# SCH_gibran_2026-04-14.net
KiCad netlist of a schematic drawn in EasyEDA
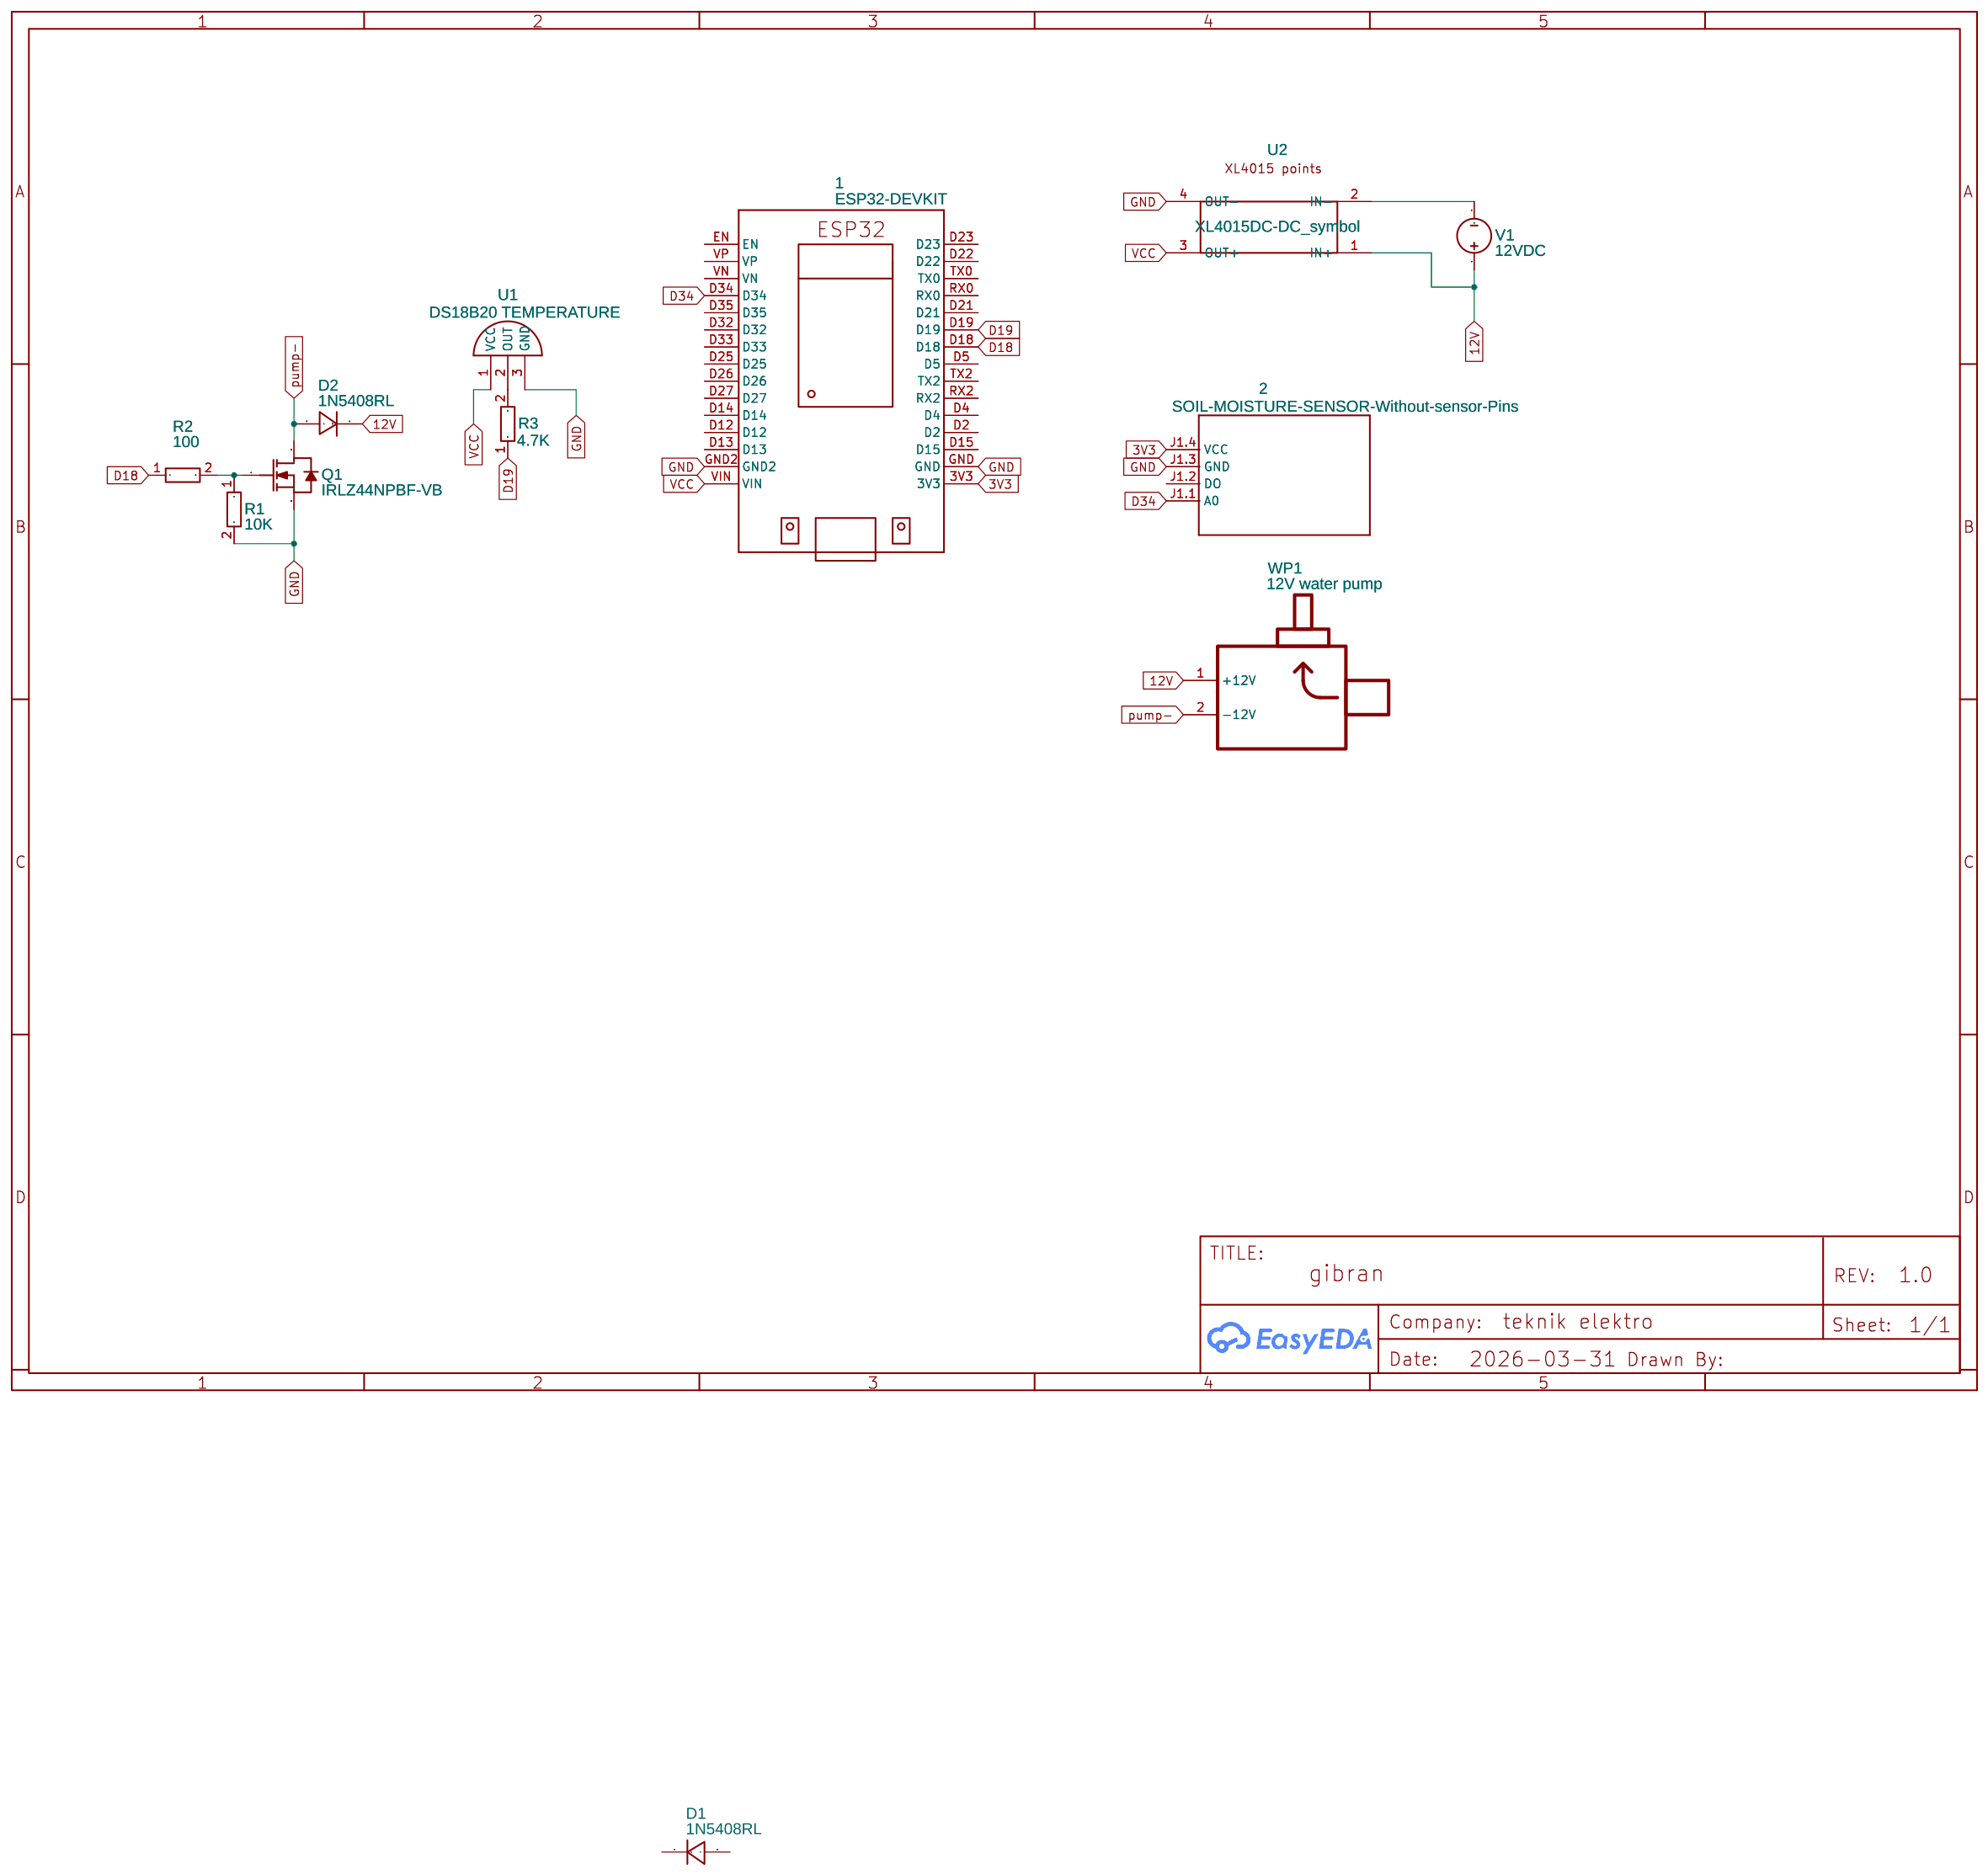
[diagram p0: schematic sheet]

(export (version "E")
  (design (tool "Eeschema 10.0.6"))
  (components
    (comp (ref "1") (value "ESP32-DEVKIT") (libsource (lib "") (part "ESP32-DEVKIT-V1-30PIN")))
    (comp (ref "2")
      (value "SOIL-MOISTURE-SENSOR-Without-sensor-Pins")
      (libsource (lib "") (part "SOIL-MOISTURE-SENSOR-Without-sensor-Pins"))
    )
    (comp (ref "D1") (value "1N5408RL") (libsource (lib "") (part "1N5408RL_1")))
    (comp (ref "D2") (value "1N5408RL") (libsource (lib "") (part "1N5408RL")))
    (comp (ref "Q1")
      (value "IRLZ44NPBF-VB")
      (fields (field (name "Manufacturer") "VBsemi(微碧半导体)"))
      (libsource (lib "") (part "IRLZ44NPBF-VB"))
    )
    (comp (ref "R1")
      (value "10K")
      (fields (field (name "Manufacturer Part") "MF1/4W-330Ω±1% T") (field (name "Manufacturer") "CCO(千志电子)"))
      (libsource (lib "") (part "10K-R-THT"))
    )
    (comp (ref "R2")
      (value "100")
      (fields (field (name "Manufacturer Part") "MF1/4W-330Ω±1% T") (field (name "Manufacturer") "CCO(千志电子)"))
      (libsource (lib "") (part "10K-R-THT_2"))
    )
    (comp (ref "R3")
      (value "4.7K")
      (fields (field (name "Manufacturer Part") "MF1/4W-330Ω±1% T") (field (name "Manufacturer") "CCO(千志电子)"))
      (libsource (lib "") (part "10K-R-THT_1"))
    )
    (comp (ref "U1")
      (value "DS18B20 TEMPERATURE")
      (fields (field (name "Manufacturer Part") "New SchematicLib"))
      (libsource (lib "") (part "DS18B20 TEMPERATURE"))
    )
    (comp (ref "U2") (value "XL4015DC-DC_symbol") (libsource (lib "") (part "XL4015DC-DC_symbol")))
    (comp (ref "V1") (value "12VDC") (libsource (lib "") (part "POWER_SUPPLY_12V COPY COPY")))
    (comp (ref "WP1") (value "12V water pump") (libsource (lib "") (part "12V water pump")))
  )
  (nets
    (net (code "1") (name "3V3") (class "Default")
      (node (ref "1") (pin "3V3") (pinfunction "3V3_3V3") (pintype "unspecified"))
      (node (ref "2") (pin "J1.4") (pinfunction "VCC_J1.4") (pintype "unspecified"))
    )
    (net (code "2") (name "12V") (class "Default")
      (node (ref "D2") (pin "1") (pinfunction "C_1") (pintype "unspecified"))
      (node (ref "U2") (pin "1") (pinfunction "IN+_1") (pintype "unspecified"))
      (node (ref "V1") (pin "1") (pinfunction "1_1") (pintype "unspecified"))
      (node (ref "WP1") (pin "1") (pinfunction "+12V_1") (pintype "unspecified"))
    )
    (net (code "3") (name "D18") (class "Default")
      (node (ref "1") (pin "D18") (pinfunction "D18_D18") (pintype "unspecified"))
      (node (ref "R2") (pin "1") (pinfunction "1_1") (pintype "unspecified"))
    )
    (net (code "4") (name "D19") (class "Default")
      (node (ref "1") (pin "D19") (pinfunction "D19_D19") (pintype "unspecified"))
      (node (ref "R3") (pin "1") (pinfunction "1_1") (pintype "unspecified"))
    )
    (net (code "5") (name "D34") (class "Default")
      (node (ref "1") (pin "D34") (pinfunction "D34_D34") (pintype "unspecified"))
      (node (ref "2") (pin "J1.1") (pinfunction "A0_J1.1") (pintype "unspecified"))
    )
    (net (code "6") (name "GND") (class "Default")
      (node (ref "1") (pin "GND") (pinfunction "GND_GND") (pintype "unspecified"))
      (node (ref "1") (pin "GND2") (pinfunction "GND2_GND2") (pintype "unspecified"))
      (node (ref "2") (pin "J1.3") (pinfunction "GND_J1.3") (pintype "unspecified"))
      (node (ref "Q1") (pin "3") (pinfunction "S_3") (pintype "unspecified"))
      (node (ref "R1") (pin "2") (pinfunction "2_2") (pintype "unspecified"))
      (node (ref "U1") (pin "3") (pinfunction "GND_3") (pintype "unspecified"))
      (node (ref "U2") (pin "4") (pinfunction "OUT-_4") (pintype "unspecified"))
    )
    (net (code "7") (name "Net-(Q1-G)") (class "Default")
      (node (ref "Q1") (pin "1") (pinfunction "G_1") (pintype "unspecified"))
      (node (ref "R1") (pin "1") (pinfunction "1_1") (pintype "unspecified"))
      (node (ref "R2") (pin "2") (pinfunction "2_2") (pintype "unspecified"))
    )
    (net (code "8") (name "Net-(U1-OUT)") (class "Default")
      (node (ref "R3") (pin "2") (pinfunction "2_2") (pintype "unspecified"))
      (node (ref "U1") (pin "2") (pinfunction "OUT_2") (pintype "unspecified"))
    )
    (net (code "9") (name "Net-(U2-IN-)") (class "Default")
      (node (ref "U2") (pin "2") (pinfunction "IN-_2") (pintype "unspecified"))
      (node (ref "V1") (pin "2") (pinfunction "2_2") (pintype "unspecified"))
    )
    (net (code "10") (name "VCC") (class "Default")
      (node (ref "1") (pin "VIN") (pinfunction "VIN_VIN") (pintype "unspecified"))
      (node (ref "U1") (pin "1") (pinfunction "VCC_1") (pintype "unspecified"))
      (node (ref "U2") (pin "3") (pinfunction "OUT+_3") (pintype "unspecified"))
    )
    (net (code "11") (name "pump-") (class "Default")
      (node (ref "D2") (pin "2") (pinfunction "A_2") (pintype "unspecified"))
      (node (ref "Q1") (pin "2") (pinfunction "D_2") (pintype "unspecified"))
      (node (ref "WP1") (pin "2") (pinfunction "-12V_2") (pintype "unspecified"))
    )
    (net (code "12") (name "unconnected-(1-PadD2)") (class "Default")
      (node (ref "1") (pin "D2") (pinfunction "D2_D2") (pintype "unspecified"))
    )
    (net (code "13") (name "unconnected-(1-PadD4)") (class "Default")
      (node (ref "1") (pin "D4") (pinfunction "D4_D4") (pintype "unspecified"))
    )
    (net (code "14") (name "unconnected-(1-PadD5)") (class "Default")
      (node (ref "1") (pin "D5") (pinfunction "D5_D5") (pintype "unspecified"))
    )
    (net (code "15") (name "unconnected-(1-PadD12)") (class "Default")
      (node (ref "1") (pin "D12") (pinfunction "D12_D12") (pintype "unspecified"))
    )
    (net (code "16") (name "unconnected-(1-PadD13)") (class "Default")
      (node (ref "1") (pin "D13") (pinfunction "D13_D13") (pintype "unspecified"))
    )
    (net (code "17") (name "unconnected-(1-PadD14)") (class "Default")
      (node (ref "1") (pin "D14") (pinfunction "D14_D14") (pintype "unspecified"))
    )
    (net (code "18") (name "unconnected-(1-PadD15)") (class "Default")
      (node (ref "1") (pin "D15") (pinfunction "D15_D15") (pintype "unspecified"))
    )
    (net (code "19") (name "unconnected-(1-PadD21)") (class "Default")
      (node (ref "1") (pin "D21") (pinfunction "D21_D21") (pintype "unspecified"))
    )
    (net (code "20") (name "unconnected-(1-PadD22)") (class "Default")
      (node (ref "1") (pin "D22") (pinfunction "D22_D22") (pintype "unspecified"))
    )
    (net (code "21") (name "unconnected-(1-PadD23)") (class "Default")
      (node (ref "1") (pin "D23") (pinfunction "D23_D23") (pintype "unspecified"))
    )
    (net (code "22") (name "unconnected-(1-PadD25)") (class "Default")
      (node (ref "1") (pin "D25") (pinfunction "D25_D25") (pintype "unspecified"))
    )
    (net (code "23") (name "unconnected-(1-PadD26)") (class "Default")
      (node (ref "1") (pin "D26") (pinfunction "D26_D26") (pintype "unspecified"))
    )
    (net (code "24") (name "unconnected-(1-PadD27)") (class "Default")
      (node (ref "1") (pin "D27") (pinfunction "D27_D27") (pintype "unspecified"))
    )
    (net (code "25") (name "unconnected-(1-PadD32)") (class "Default")
      (node (ref "1") (pin "D32") (pinfunction "D32_D32") (pintype "unspecified"))
    )
    (net (code "26") (name "unconnected-(1-PadD33)") (class "Default")
      (node (ref "1") (pin "D33") (pinfunction "D33_D33") (pintype "unspecified"))
    )
    (net (code "27") (name "unconnected-(1-PadD35)") (class "Default")
      (node (ref "1") (pin "D35") (pinfunction "D35_D35") (pintype "unspecified"))
    )
    (net (code "28") (name "unconnected-(1-PadEN)") (class "Default")
      (node (ref "1") (pin "EN") (pinfunction "EN_EN") (pintype "unspecified"))
    )
    (net (code "29") (name "unconnected-(1-PadRX0)") (class "Default")
      (node (ref "1") (pin "RX0") (pinfunction "RX0_RX0") (pintype "unspecified"))
    )
    (net (code "30") (name "unconnected-(1-PadRX2)") (class "Default")
      (node (ref "1") (pin "RX2") (pinfunction "RX2_RX2") (pintype "unspecified"))
    )
    (net (code "31") (name "unconnected-(1-PadTX0)") (class "Default")
      (node (ref "1") (pin "TX0") (pinfunction "TX0_TX0") (pintype "unspecified"))
    )
    (net (code "32") (name "unconnected-(1-PadTX2)") (class "Default")
      (node (ref "1") (pin "TX2") (pinfunction "TX2_TX2") (pintype "unspecified"))
    )
    (net (code "33") (name "unconnected-(1-PadVN)") (class "Default")
      (node (ref "1") (pin "VN") (pinfunction "VN_VN") (pintype "unspecified"))
    )
    (net (code "34") (name "unconnected-(1-PadVP)") (class "Default")
      (node (ref "1") (pin "VP") (pinfunction "VP_VP") (pintype "unspecified"))
    )
    (net (code "35") (name "unconnected-(2-DO-PadJ1.2)") (class "Default")
      (node (ref "2") (pin "J1.2") (pinfunction "DO_J1.2") (pintype "unspecified"))
    )
    (net (code "36") (name "unconnected-(D1-A-Pad2)") (class "Default")
      (node (ref "D1") (pin "2") (pinfunction "A_2") (pintype "unspecified"))
    )
    (net (code "37") (name "unconnected-(D1-C-Pad1)") (class "Default")
      (node (ref "D1") (pin "1") (pinfunction "C_1") (pintype "unspecified"))
    )
  )
)
